# MainBoard_PERIPH.net
KiCad netlist of a schematic drawn in Altium Designer
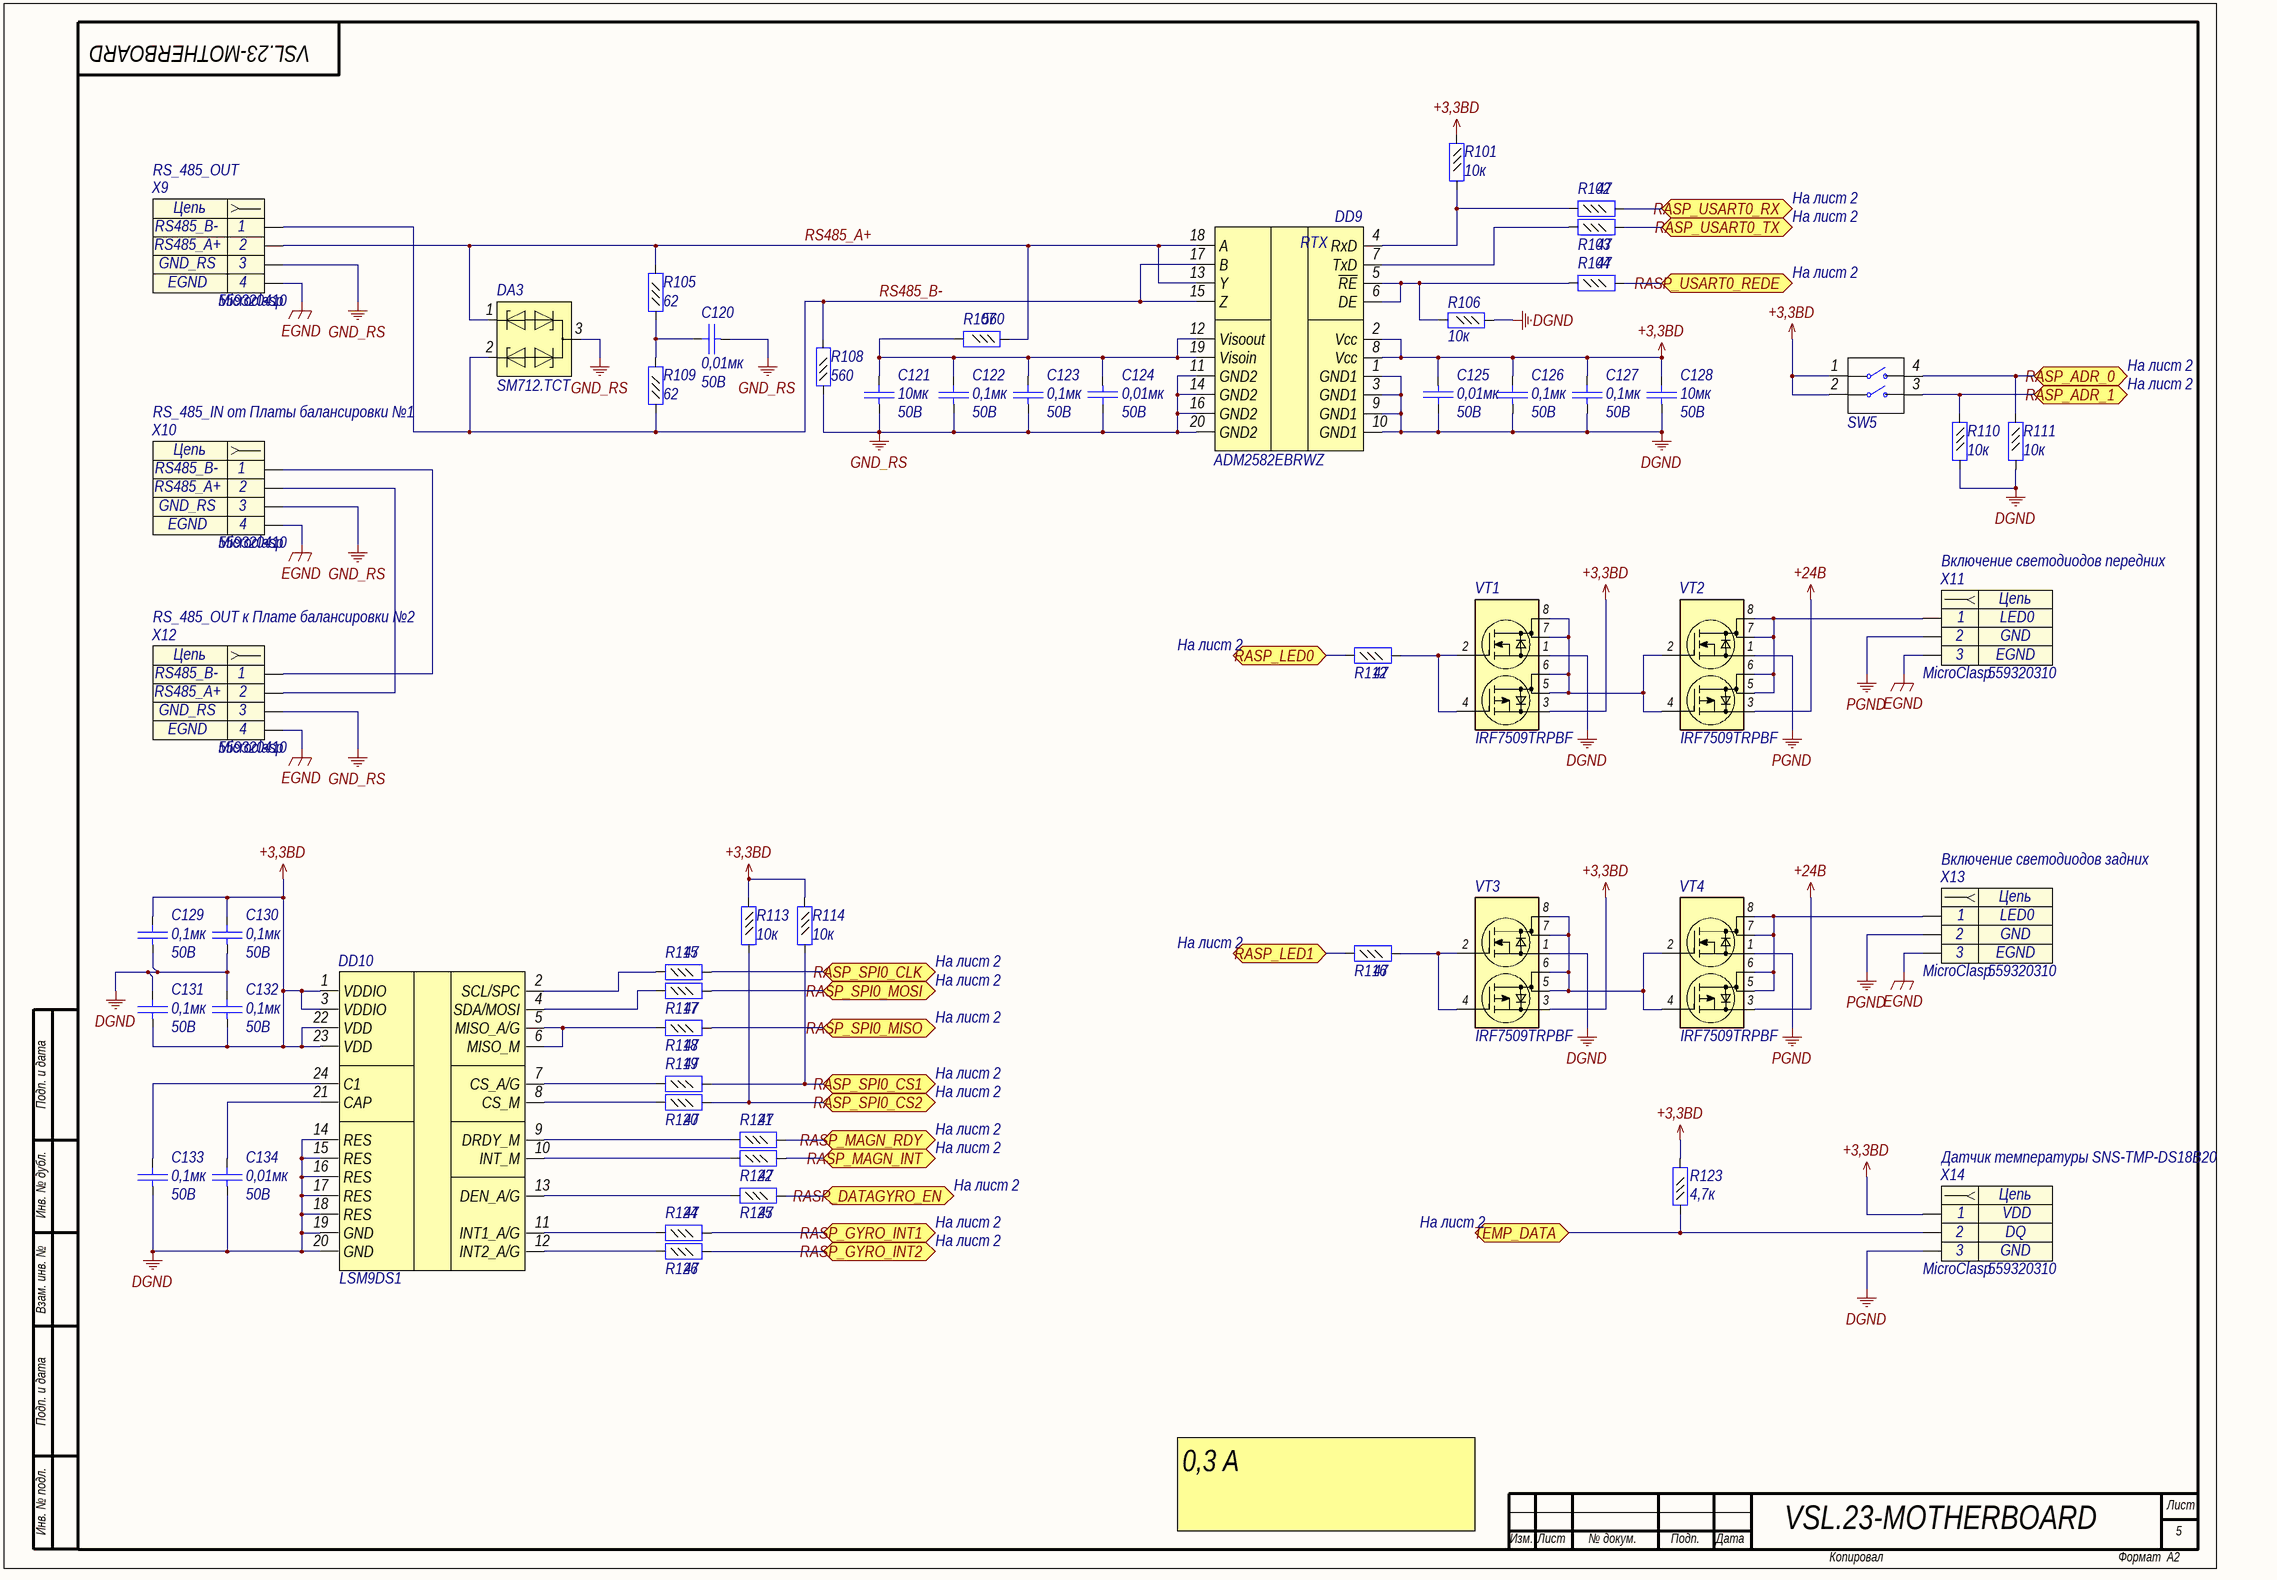
[diagram p0: MainBoard_PERIPH.SchDoc]

(export (version "E")
  (design (tool "Eeschema 10.0.6"))
  (components
    (comp (ref "C120")
      (value "0,01мк")
      (footprint "C0402")
      (description "Конденсатор")
      (fields
        (field (name "VOLTAGE") "50B")
        (field (name "PART NUMBER") "GRM155R71H103K")
        (field (name "Comment") "Capacitor")
      )
      (libsource (lib "MOP44") (part "Capacitor"))
    )
    (comp (ref "C121")
      (value "10мк")
      (footprint "C1210")
      (description "Конденсатор")
      (fields (field (name "VOLTAGE") "50В") (field (name "PART NUMBER") "C3225X7R1H106K250AC"))
      (libsource (lib "MOP44") (part "Capacitor"))
    )
    (comp (ref "C122")
      (value "0,1мк")
      (footprint "C0402")
      (description "Конденсатор")
      (fields
        (field (name "VOLTAGE") "50В")
        (field (name "PART NUMBER") "GRM155R71H104KE14D ")
        (field (name "Comment") "Capacitor")
      )
      (libsource (lib "MOP44") (part "Capacitor"))
    )
    (comp (ref "C123")
      (value "0,1мк")
      (footprint "C0402")
      (description "Конденсатор")
      (fields
        (field (name "VOLTAGE") "50В")
        (field (name "PART NUMBER") "GRM155R71H104KE14D ")
        (field (name "Comment") "Capacitor")
      )
      (libsource (lib "MOP44") (part "Capacitor"))
    )
    (comp (ref "C124")
      (value "0,01мк")
      (footprint "C0402")
      (description "Конденсатор")
      (fields (field (name "VOLTAGE") "50B") (field (name "PART NUMBER") "GRM155R71H103K"))
      (libsource (lib "MOP44") (part "Capacitor"))
    )
    (comp (ref "C125")
      (value "0,01мк")
      (footprint "C0402")
      (description "Конденсатор")
      (fields (field (name "VOLTAGE") "50B") (field (name "PART NUMBER") "GRM155R71H103K"))
      (libsource (lib "MOP44") (part "Capacitor"))
    )
    (comp (ref "C126")
      (value "0,1мк")
      (footprint "C0402")
      (description "Конденсатор")
      (fields
        (field (name "VOLTAGE") "50В")
        (field (name "PART NUMBER") "GRM155R71H104KE14D ")
        (field (name "Comment") "Capacitor")
      )
      (libsource (lib "MOP44") (part "Capacitor"))
    )
    (comp (ref "C127")
      (value "0,1мк")
      (footprint "C0402")
      (description "Конденсатор")
      (fields
        (field (name "VOLTAGE") "50В")
        (field (name "PART NUMBER") "GRM155R71H104KE14D ")
        (field (name "Comment") "Capacitor")
      )
      (libsource (lib "MOP44") (part "Capacitor"))
    )
    (comp (ref "C128")
      (value "10мк")
      (footprint "C1210")
      (description "Конденсатор")
      (fields (field (name "VOLTAGE") "50В") (field (name "PART NUMBER") "C3225X7R1H106K250AC"))
      (libsource (lib "MOP44") (part "Capacitor"))
    )
    (comp (ref "C129")
      (value "0,1мк")
      (footprint "C0402")
      (description "Конденсатор")
      (fields
        (field (name "VOLTAGE") "50В")
        (field (name "PART NUMBER") "GRM155R71H104KE14D ")
        (field (name "Comment") "Capacitor")
      )
      (libsource (lib "MOP44") (part "Capacitor"))
    )
    (comp (ref "C130")
      (value "0,1мк")
      (footprint "C0402")
      (description "Конденсатор")
      (fields
        (field (name "VOLTAGE") "50В")
        (field (name "PART NUMBER") "GRM155R71H104KE14D ")
        (field (name "Comment") "Capacitor")
      )
      (libsource (lib "MOP44") (part "Capacitor"))
    )
    (comp (ref "C131")
      (value "0,1мк")
      (footprint "C0402")
      (description "Конденсатор")
      (fields
        (field (name "VOLTAGE") "50В")
        (field (name "PART NUMBER") "GRM155R71H104KE14D ")
        (field (name "Comment") "Capacitor")
      )
      (libsource (lib "MOP44") (part "Capacitor"))
    )
    (comp (ref "C132")
      (value "0,1мк")
      (footprint "C0402")
      (description "Конденсатор")
      (fields
        (field (name "VOLTAGE") "50В")
        (field (name "PART NUMBER") "GRM155R71H104KE14D ")
        (field (name "Comment") "Capacitor")
      )
      (libsource (lib "MOP44") (part "Capacitor"))
    )
    (comp (ref "C133")
      (value "0,1мк")
      (footprint "C0402")
      (description "Конденсатор")
      (fields
        (field (name "VOLTAGE") "50В")
        (field (name "PART NUMBER") "GRM155R71H104KE14D ")
        (field (name "Comment") "Capacitor")
      )
      (libsource (lib "MOP44") (part "Capacitor"))
    )
    (comp (ref "C134")
      (value "0,01мк")
      (footprint "C0402")
      (description "Конденсатор")
      (fields (field (name "VOLTAGE") "50B") (field (name "PART NUMBER") "GRM155R71H103K"))
      (libsource (lib "MOP44") (part "Capacitor"))
    )
    (comp (ref "DA3")
      (value "SM712")
      (footprint "SOT23-3")
      (description "TVS")
      (fields (field (name "PART NUMBER") "SM712.TCT"))
      (libsource (lib "MOP44") (part "SM712"))
    )
    (comp (ref "DD9")
      (value "~")
      (footprint "SO20W")
      (description "Приемопередатчик RS485 изолированный")
      (fields (field (name "PART NUMBER") "ADM2582EBRWZ"))
      (libsource (lib "MOP44") (part "ADM2582E"))
    )
    (comp (ref "DD10")
      (value "LSM9DS1")
      (footprint "LGA24")
      (description "3D accelerometer, 3D gyroscope, 3D magnetometer")
      (libsource (lib "MOP44") (part "LSM9DS1"))
    )
    (comp (ref "R101")
      (value "10к")
      (footprint "R0402")
      (description "Резистор")
      (fields (field (name "PART NUMBER") "RC0402FR-0710KL") (field (name "POWER") "0,062Вт"))
      (libsource (lib "") (part "Resistor_0,062Вт_2"))
    )
    (comp (ref "R102")
      (value "47")
      (footprint "R0402")
      (description "Резистор")
      (fields (field (name "PART NUMBER") "RC0402FR-0747RL") (field (name "POWER") "0,062Вт"))
      (libsource (lib "MOP44") (part "Resistor_0,062Вт"))
    )
    (comp (ref "R103")
      (value "47")
      (footprint "R0402")
      (description "Резистор")
      (fields (field (name "PART NUMBER") "RC0402FR-0747RL") (field (name "POWER") "0,062Вт"))
      (libsource (lib "MOP44") (part "Resistor_0,062Вт"))
    )
    (comp (ref "R104")
      (value "47")
      (footprint "R0402")
      (description "Резистор")
      (fields (field (name "PART NUMBER") "RC0402FR-0747RL") (field (name "POWER") "0,062Вт"))
      (libsource (lib "MOP44") (part "Resistor_0,062Вт"))
    )
    (comp (ref "R105")
      (value "62")
      (footprint "R0402")
      (description "Резистор")
      (fields (field (name "PART NUMBER") "RC0402FR-0762RL") (field (name "POWER") "0,062Вт"))
      (libsource (lib "MOP44") (part "Resistor_0,062Вт"))
    )
    (comp (ref "R106")
      (value "10к")
      (footprint "R0402")
      (description "Резистор")
      (fields (field (name "PART NUMBER") "RC0402FR-0710KL") (field (name "POWER") "0,062Вт"))
      (libsource (lib "") (part "Resistor_0,062Вт_1"))
    )
    (comp (ref "R107")
      (value "560")
      (footprint "R0402")
      (description "Резистор")
      (fields (field (name "PART NUMBER") "RC0402FR-07560RL") (field (name "POWER") "0,062Вт"))
      (libsource (lib "") (part "Resistor_0,062Вт_1"))
    )
    (comp (ref "R108")
      (value "560")
      (footprint "R0402")
      (description "Резистор")
      (fields (field (name "PART NUMBER") "RC0402FR-07560RL") (field (name "POWER") "0,062Вт"))
      (libsource (lib "") (part "Resistor_0,062Вт_3"))
    )
    (comp (ref "R109")
      (value "62")
      (footprint "R0402")
      (description "Резистор")
      (fields (field (name "PART NUMBER") "RC0402FR-0762RL") (field (name "POWER") "0,062Вт"))
      (libsource (lib "MOP44") (part "Resistor_0,062Вт"))
    )
    (comp (ref "R110")
      (value "10к")
      (footprint "R0402")
      (description "Резистор")
      (fields (field (name "PART NUMBER") "RC0402FR-0710KL") (field (name "POWER") "0,062Вт"))
      (libsource (lib "") (part "Resistor_0,062Вт_2"))
    )
    (comp (ref "R111")
      (value "10к")
      (footprint "R0402")
      (description "Резистор")
      (fields (field (name "PART NUMBER") "RC0402FR-0710KL") (field (name "POWER") "0,062Вт"))
      (libsource (lib "") (part "Resistor_0,062Вт_2"))
    )
    (comp (ref "R112")
      (value "47")
      (footprint "R0402")
      (description "Резистор")
      (fields (field (name "PART NUMBER") "RC0402FR-0747RL") (field (name "POWER") "0,062Вт"))
      (libsource (lib "MOP44") (part "Resistor_0,062Вт"))
    )
    (comp (ref "R113")
      (value "10к")
      (footprint "R0402")
      (description "Резистор")
      (fields (field (name "PART NUMBER") "RC0402FR-0710KL") (field (name "POWER") "0,062Вт"))
      (libsource (lib "") (part "Resistor_0,062Вт_2"))
    )
    (comp (ref "R114")
      (value "10к")
      (footprint "R0402")
      (description "Резистор")
      (fields (field (name "PART NUMBER") "RC0402FR-0710KL") (field (name "POWER") "0,062Вт"))
      (libsource (lib "") (part "Resistor_0,062Вт_2"))
    )
    (comp (ref "R115")
      (value "47")
      (footprint "R0402")
      (description "Резистор")
      (fields (field (name "PART NUMBER") "RC0402FR-0747RL") (field (name "POWER") "0,062Вт"))
      (libsource (lib "MOP44") (part "Resistor_0,062Вт"))
    )
    (comp (ref "R116")
      (value "47")
      (footprint "R0402")
      (description "Резистор")
      (fields (field (name "PART NUMBER") "RC0402FR-0747RL") (field (name "POWER") "0,062Вт"))
      (libsource (lib "MOP44") (part "Resistor_0,062Вт"))
    )
    (comp (ref "R117")
      (value "47")
      (footprint "R0402")
      (description "Резистор")
      (fields (field (name "PART NUMBER") "RC0402FR-0747RL") (field (name "POWER") "0,062Вт"))
      (libsource (lib "MOP44") (part "Resistor_0,062Вт"))
    )
    (comp (ref "R118")
      (value "47")
      (footprint "R0402")
      (description "Резистор")
      (fields (field (name "PART NUMBER") "RC0402FR-0747RL") (field (name "POWER") "0,062Вт"))
      (libsource (lib "MOP44") (part "Resistor_0,062Вт"))
    )
    (comp (ref "R119")
      (value "47")
      (footprint "R0402")
      (description "Резистор")
      (fields (field (name "PART NUMBER") "RC0402FR-0747RL") (field (name "POWER") "0,062Вт"))
      (libsource (lib "MOP44") (part "Resistor_0,062Вт"))
    )
    (comp (ref "R120")
      (value "47")
      (footprint "R0402")
      (description "Резистор")
      (fields (field (name "PART NUMBER") "RC0402FR-0747RL") (field (name "POWER") "0,062Вт"))
      (libsource (lib "MOP44") (part "Resistor_0,062Вт"))
    )
    (comp (ref "R121")
      (value "47")
      (footprint "R0402")
      (description "Резистор")
      (fields (field (name "PART NUMBER") "RC0402FR-0747RL") (field (name "POWER") "0,062Вт"))
      (libsource (lib "MOP44") (part "Resistor_0,062Вт"))
    )
    (comp (ref "R122")
      (value "47")
      (footprint "R0402")
      (description "Резистор")
      (fields (field (name "PART NUMBER") "RC0402FR-0747RL") (field (name "POWER") "0,062Вт"))
      (libsource (lib "MOP44") (part "Resistor_0,062Вт"))
    )
    (comp (ref "R123")
      (value "4,7к")
      (footprint "R0402")
      (description "Резистор")
      (fields (field (name "PART NUMBER") "RC0402FR-074K7") (field (name "POWER") "0,062Вт"))
      (libsource (lib "") (part "Resistor_0,062Вт_3"))
    )
    (comp (ref "R124")
      (value "47")
      (footprint "R0402")
      (description "Резистор")
      (fields (field (name "PART NUMBER") "RC0402FR-0747RL") (field (name "POWER") "0,062Вт"))
      (libsource (lib "MOP44") (part "Resistor_0,062Вт"))
    )
    (comp (ref "R125")
      (value "47")
      (footprint "R0402")
      (description "Резистор")
      (fields (field (name "PART NUMBER") "RC0402FR-0747RL") (field (name "POWER") "0,062Вт"))
      (libsource (lib "MOP44") (part "Resistor_0,062Вт"))
    )
    (comp (ref "R126")
      (value "47")
      (footprint "R0402")
      (description "Резистор")
      (fields (field (name "PART NUMBER") "RC0402FR-0747RL") (field (name "POWER") "0,062Вт"))
      (libsource (lib "MOP44") (part "Resistor_0,062Вт"))
    )
    (comp (ref "SW5")
      (value "DS1040-02")
      (footprint "2PAD_ADR")
      (description "DIP переключатель")
      (libsource (lib "MOP44") (part "DS1040-02"))
    )
    (comp (ref "VT1")
      (value "IRF7509TRPBF")
      (footprint "Micro8")
      (description "Комплементарная сборка МОП")
      (fields
        (field (name "PART NUMBER") "IRF7509TRPBF")
        (field (name "MANUFACTURER") "International Rectifier")
      )
      (libsource (lib "MOP44") (part "IRF7509TRPBF"))
    )
    (comp (ref "VT2")
      (value "IRF7509TRPBF")
      (footprint "Micro8")
      (description "Комплементарная сборка МОП")
      (fields
        (field (name "PART NUMBER") "IRF7509TRPBF")
        (field (name "MANUFACTURER") "International Rectifier")
      )
      (libsource (lib "MOP44") (part "IRF7509TRPBF"))
    )
    (comp (ref "VT3")
      (value "IRF7509TRPBF")
      (footprint "Micro8")
      (description "Комплементарная сборка МОП")
      (fields
        (field (name "PART NUMBER") "IRF7509TRPBF")
        (field (name "MANUFACTURER") "International Rectifier")
      )
      (libsource (lib "MOP44") (part "IRF7509TRPBF"))
    )
    (comp (ref "VT4")
      (value "IRF7509TRPBF")
      (footprint "Micro8")
      (description "Комплементарная сборка МОП")
      (fields
        (field (name "PART NUMBER") "IRF7509TRPBF")
        (field (name "MANUFACTURER") "International Rectifier")
      )
      (libsource (lib "MOP44") (part "IRF7509TRPBF"))
    )
    (comp (ref "X9")
      (value "RS_485_OUT")
      (footprint "MOLEX_559320410")
      (description "Разъем - 4 конт. розетка")
      (fields (field (name "PART NUMBER") "559320410"))
      (libsource (lib "MOP44") (part "Header_4_sct"))
    )
    (comp (ref "X10")
      (value "RS_485_IN от Платы балансировки №1")
      (footprint "MOLEX_559320410")
      (description "Разъем - 4 конт. розетка")
      (fields (field (name "PART NUMBER") "559320410"))
      (libsource (lib "MOP44") (part "Header_4_sct"))
    )
    (comp (ref "X11")
      (value "Включение светодиодов передних")
      (footprint "MOLEX_559320310")
      (description "Разъем - 3 конт. розетка")
      (fields (field (name "PART NAME") "MicroClasp") (field (name "PART NUMBER") "559320310"))
      (libsource (lib "MOP44") (part "Header_3_sct"))
    )
    (comp (ref "X12")
      (value "RS_485_OUT к Плате балансировки №2")
      (footprint "MOLEX_559320410")
      (description "Разъем - 4 конт. розетка")
      (fields (field (name "PART NUMBER") "559320410"))
      (libsource (lib "MOP44") (part "Header_4_sct"))
    )
    (comp (ref "X13")
      (value "Включение светодиодов задних")
      (footprint "MOLEX_559320310")
      (description "Разъем - 3 конт. розетка")
      (fields (field (name "PART NAME") "MicroClasp") (field (name "PART NUMBER") "559320310"))
      (libsource (lib "MOP44") (part "Header_3_sct"))
    )
    (comp (ref "X14")
      (value "Датчик температуры SNS-TMP-DS18B20")
      (footprint "MOLEX_559320310")
      (description "Разъем - 3 конт. розетка")
      (fields (field (name "PART NAME") "MicroClasp") (field (name "PART NUMBER") "559320310"))
      (libsource (lib "MOP44") (part "Header_3_sct"))
    )
  )
  (nets
    (net (code "1") (name "+3,3BD") (class "Default")
      (node (ref "C125") (pin "1") (pinfunction "1_1") (pintype "passive"))
      (node (ref "C126") (pin "2") (pinfunction "2_2") (pintype "passive"))
      (node (ref "C127") (pin "2") (pinfunction "2_2") (pintype "passive"))
      (node (ref "C128") (pin "2") (pinfunction "2_2") (pintype "passive"))
      (node (ref "C129") (pin "2") (pinfunction "2_2") (pintype "passive"))
      (node (ref "C130") (pin "2") (pinfunction "2_2") (pintype "passive"))
      (node (ref "C131") (pin "1") (pinfunction "1_1") (pintype "passive"))
      (node (ref "C132") (pin "1") (pinfunction "1_1") (pintype "passive"))
      (node (ref "DD10") (pin "1") (pinfunction "VDDIO_1") (pintype "passive"))
      (node (ref "DD10") (pin "22") (pinfunction "VDD_22") (pintype "passive"))
      (node (ref "DD10") (pin "23") (pinfunction "VDD_23") (pintype "passive"))
      (node (ref "DD10") (pin "3") (pinfunction "VDDIO_3") (pintype "passive"))
      (node (ref "DD9") (pin "2") (pinfunction "Vcc_2") (pintype "passive"))
      (node (ref "DD9") (pin "8") (pinfunction "Vcc_8") (pintype "passive"))
      (node (ref "R101") (pin "1") (pinfunction "1_1") (pintype "passive"))
      (node (ref "R113") (pin "1") (pinfunction "1_1") (pintype "passive"))
      (node (ref "R114") (pin "1") (pinfunction "1_1") (pintype "passive"))
      (node (ref "R123") (pin "2") (pinfunction "2_2") (pintype "passive"))
      (node (ref "SW5") (pin "1") (pintype "passive"))
      (node (ref "SW5") (pin "2") (pintype "passive"))
      (node (ref "VT1") (pin "3") (pinfunction "S2_3") (pintype "passive"))
      (node (ref "VT3") (pin "3") (pinfunction "S2_3") (pintype "passive"))
      (node (ref "X14") (pin "1") (pinfunction "1_1") (pintype "passive"))
    )
    (net (code "2") (name "+24B") (class "Default")
      (node (ref "VT2") (pin "3") (pinfunction "S2_3") (pintype "passive"))
      (node (ref "VT4") (pin "3") (pinfunction "S2_3") (pintype "passive"))
    )
    (net (code "3") (name "/RASP_ADR_0") (class "Default")
      (node (ref "R111") (pin "1") (pinfunction "1_1") (pintype "passive"))
      (node (ref "SW5") (pin "4") (pintype "passive"))
    )
    (net (code "4") (name "/RASP_ADR_1") (class "Default")
      (node (ref "R110") (pin "1") (pinfunction "1_1") (pintype "passive"))
      (node (ref "SW5") (pin "3") (pintype "passive"))
    )
    (net (code "5") (name "/RASP_DATAGYRO_EN") (class "Default")
      (node (ref "R125") (pin "2") (pinfunction "2_2") (pintype "passive"))
    )
    (net (code "6") (name "/RASP_GYRO_INT1") (class "Default")
      (node (ref "R124") (pin "2") (pinfunction "2_2") (pintype "passive"))
    )
    (net (code "7") (name "/RASP_GYRO_INT2") (class "Default")
      (node (ref "R126") (pin "2") (pinfunction "2_2") (pintype "passive"))
    )
    (net (code "8") (name "/RASP_LED0") (class "Default")
      (node (ref "R112") (pin "1") (pinfunction "1_1") (pintype "passive"))
    )
    (net (code "9") (name "/RASP_LED1") (class "Default")
      (node (ref "R116") (pin "1") (pinfunction "1_1") (pintype "passive"))
    )
    (net (code "10") (name "/RASP_MAGN_INT") (class "Default")
      (node (ref "R122") (pin "2") (pinfunction "2_2") (pintype "passive"))
    )
    (net (code "11") (name "/RASP_MAGN_RDY") (class "Default")
      (node (ref "R121") (pin "2") (pinfunction "2_2") (pintype "passive"))
    )
    (net (code "12") (name "/RASP_SPI0_CLK") (class "Default")
      (node (ref "R115") (pin "2") (pinfunction "2_2") (pintype "passive"))
    )
    (net (code "13") (name "/RASP_SPI0_CS1") (class "Default")
      (node (ref "R114") (pin "2") (pinfunction "2_2") (pintype "passive"))
      (node (ref "R119") (pin "2") (pinfunction "2_2") (pintype "passive"))
    )
    (net (code "14") (name "/RASP_SPI0_CS2") (class "Default")
      (node (ref "R113") (pin "2") (pinfunction "2_2") (pintype "passive"))
      (node (ref "R120") (pin "2") (pinfunction "2_2") (pintype "passive"))
    )
    (net (code "15") (name "/RASP_SPI0_MISO") (class "Default")
      (node (ref "R118") (pin "2") (pinfunction "2_2") (pintype "passive"))
    )
    (net (code "16") (name "/RASP_SPI0_MOSI") (class "Default")
      (node (ref "R117") (pin "2") (pinfunction "2_2") (pintype "passive"))
    )
    (net (code "17") (name "/RASP_USART0_REDE") (class "Default")
      (node (ref "R104") (pin "2") (pinfunction "2_2") (pintype "passive"))
    )
    (net (code "18") (name "/RASP_USART0_RX") (class "Default")
      (node (ref "R102") (pin "2") (pinfunction "2_2") (pintype "passive"))
    )
    (net (code "19") (name "/RASP_USART0_TX") (class "Default")
      (node (ref "R103") (pin "2") (pinfunction "2_2") (pintype "passive"))
    )
    (net (code "20") (name "/RS485_A+") (class "Default")
      (node (ref "DA3") (pin "1") (pintype "passive"))
      (node (ref "DD9") (pin "13") (pinfunction "Y_13") (pintype "passive"))
      (node (ref "DD9") (pin "18") (pinfunction "A_18") (pintype "passive"))
      (node (ref "R105") (pin "2") (pinfunction "2_2") (pintype "passive"))
      (node (ref "R107") (pin "1") (pinfunction "1_1") (pintype "passive"))
      (node (ref "X9") (pin "2") (pinfunction "2_2") (pintype "passive"))
    )
    (net (code "21") (name "/RS485_B-") (class "Default")
      (node (ref "DA3") (pin "2") (pinfunction "1_2") (pintype "passive"))
      (node (ref "DD9") (pin "15") (pinfunction "Z_15") (pintype "passive"))
      (node (ref "DD9") (pin "17") (pinfunction "B_17") (pintype "passive"))
      (node (ref "R108") (pin "2") (pinfunction "2_2") (pintype "passive"))
      (node (ref "R109") (pin "1") (pinfunction "1_1") (pintype "passive"))
      (node (ref "X9") (pin "1") (pinfunction "1_1") (pintype "passive"))
    )
    (net (code "22") (name "/TEMP_DATA") (class "Default")
      (node (ref "R123") (pin "1") (pinfunction "1_1") (pintype "passive"))
      (node (ref "X14") (pin "2") (pinfunction "2_2") (pintype "passive"))
    )
    (net (code "23") (name "DGND") (class "Default")
      (node (ref "C125") (pin "2") (pinfunction "2_2") (pintype "passive"))
      (node (ref "C126") (pin "1") (pinfunction "1_1") (pintype "passive"))
      (node (ref "C127") (pin "1") (pinfunction "1_1") (pintype "passive"))
      (node (ref "C128") (pin "1") (pinfunction "1_1") (pintype "passive"))
      (node (ref "C129") (pin "1") (pinfunction "1_1") (pintype "passive"))
      (node (ref "C130") (pin "1") (pinfunction "1_1") (pintype "passive"))
      (node (ref "C131") (pin "2") (pinfunction "2_2") (pintype "passive"))
      (node (ref "C132") (pin "2") (pinfunction "2_2") (pintype "passive"))
      (node (ref "C133") (pin "1") (pinfunction "1_1") (pintype "passive"))
      (node (ref "C134") (pin "1") (pinfunction "1_1") (pintype "passive"))
      (node (ref "DD10") (pin "14") (pinfunction "RES_14") (pintype "passive"))
      (node (ref "DD10") (pin "15") (pinfunction "RES_15") (pintype "passive"))
      (node (ref "DD10") (pin "16") (pinfunction "RES_16") (pintype "passive"))
      (node (ref "DD10") (pin "17") (pinfunction "RES_17") (pintype "passive"))
      (node (ref "DD10") (pin "18") (pinfunction "RES_18") (pintype "passive"))
      (node (ref "DD10") (pin "19") (pinfunction "GND_19") (pintype "passive"))
      (node (ref "DD10") (pin "20") (pinfunction "GND_20") (pintype "passive"))
      (node (ref "DD9") (pin "1") (pinfunction "GND1_1") (pintype "passive"))
      (node (ref "DD9") (pin "10") (pinfunction "GND1_10") (pintype "passive"))
      (node (ref "DD9") (pin "3") (pinfunction "GND1_3") (pintype "passive"))
      (node (ref "DD9") (pin "9") (pinfunction "GND1_9") (pintype "passive"))
      (node (ref "R106") (pin "1") (pinfunction "1_1") (pintype "passive"))
      (node (ref "R110") (pin "2") (pinfunction "2_2") (pintype "passive"))
      (node (ref "R111") (pin "2") (pinfunction "2_2") (pintype "passive"))
      (node (ref "VT1") (pin "1") (pinfunction "S1_1") (pintype "passive"))
      (node (ref "VT3") (pin "1") (pinfunction "S1_1") (pintype "passive"))
      (node (ref "X14") (pin "3") (pinfunction "3_3") (pintype "passive"))
    )
    (net (code "24") (name "EGND") (class "Default")
      (node (ref "X10") (pin "4") (pinfunction "4_4") (pintype "passive"))
      (node (ref "X11") (pin "3") (pinfunction "3_3") (pintype "passive"))
      (node (ref "X12") (pin "4") (pinfunction "4_4") (pintype "passive"))
      (node (ref "X13") (pin "3") (pinfunction "3_3") (pintype "passive"))
      (node (ref "X9") (pin "4") (pinfunction "4_4") (pintype "passive"))
    )
    (net (code "25") (name "GND_RS") (class "Default")
      (node (ref "C120") (pin "1") (pinfunction "1_1") (pintype "passive"))
      (node (ref "C121") (pin "1") (pinfunction "1_1") (pintype "passive"))
      (node (ref "C122") (pin "1") (pinfunction "1_1") (pintype "passive"))
      (node (ref "C123") (pin "1") (pinfunction "1_1") (pintype "passive"))
      (node (ref "C124") (pin "2") (pinfunction "2_2") (pintype "passive"))
      (node (ref "DA3") (pin "3") (pintype "passive"))
      (node (ref "DD9") (pin "11") (pinfunction "GND2_11") (pintype "passive"))
      (node (ref "DD9") (pin "14") (pinfunction "GND2_14") (pintype "passive"))
      (node (ref "DD9") (pin "16") (pinfunction "GND2_16") (pintype "passive"))
      (node (ref "DD9") (pin "20") (pinfunction "GND2_20") (pintype "passive"))
      (node (ref "R108") (pin "1") (pinfunction "1_1") (pintype "passive"))
      (node (ref "X10") (pin "3") (pinfunction "3_3") (pintype "passive"))
      (node (ref "X12") (pin "3") (pinfunction "3_3") (pintype "passive"))
      (node (ref "X9") (pin "3") (pinfunction "3_3") (pintype "passive"))
    )
    (net (code "26") (name "Net-(C120-Pad2)") (class "Default")
      (node (ref "C120") (pin "2") (pinfunction "2_2") (pintype "passive"))
      (node (ref "R105") (pin "1") (pinfunction "1_1") (pintype "passive"))
      (node (ref "R109") (pin "2") (pinfunction "2_2") (pintype "passive"))
    )
    (net (code "27") (name "Net-(DD9-DE)") (class "Default")
      (node (ref "DD9") (pin "5") (pinfunction "~{RE}_5") (pintype "passive"))
      (node (ref "DD9") (pin "6") (pinfunction "DE_6") (pintype "passive"))
      (node (ref "R104") (pin "1") (pinfunction "1_1") (pintype "passive"))
      (node (ref "R106") (pin "2") (pinfunction "2_2") (pintype "passive"))
    )
    (net (code "28") (name "Net-(DD9-RxD)") (class "Default")
      (node (ref "DD9") (pin "4") (pinfunction "RxD_4") (pintype "passive"))
      (node (ref "R101") (pin "2") (pinfunction "2_2") (pintype "passive"))
      (node (ref "R102") (pin "1") (pinfunction "1_1") (pintype "passive"))
    )
    (net (code "29") (name "Net-(DD9-TxD)") (class "Default")
      (node (ref "DD9") (pin "7") (pinfunction "TxD_7") (pintype "passive"))
      (node (ref "R103") (pin "1") (pinfunction "1_1") (pintype "passive"))
    )
    (net (code "30") (name "Net-(DD9-Visoin)") (class "Default")
      (node (ref "C121") (pin "2") (pinfunction "2_2") (pintype "passive"))
      (node (ref "C122") (pin "2") (pinfunction "2_2") (pintype "passive"))
      (node (ref "C123") (pin "2") (pinfunction "2_2") (pintype "passive"))
      (node (ref "C124") (pin "1") (pinfunction "1_1") (pintype "passive"))
      (node (ref "DD9") (pin "12") (pinfunction "Visoout_12") (pintype "passive"))
      (node (ref "DD9") (pin "19") (pinfunction "Visoin_19") (pintype "passive"))
      (node (ref "R107") (pin "2") (pinfunction "2_2") (pintype "passive"))
    )
    (net (code "31") (name "Net-(DD10-C1)") (class "Default")
      (node (ref "C133") (pin "2") (pinfunction "2_2") (pintype "passive"))
      (node (ref "DD10") (pin "24") (pinfunction "C1_24") (pintype "passive"))
    )
    (net (code "32") (name "Net-(DD10-CAP)") (class "Default")
      (node (ref "C134") (pin "2") (pinfunction "2_2") (pintype "passive"))
      (node (ref "DD10") (pin "21") (pinfunction "CAP_21") (pintype "passive"))
    )
    (net (code "33") (name "Net-(DD10-CS_A{slash}G)") (class "Default")
      (node (ref "DD10") (pin "7") (pinfunction "CS_A/G_7") (pintype "passive"))
      (node (ref "R119") (pin "1") (pinfunction "1_1") (pintype "passive"))
    )
    (net (code "34") (name "Net-(DD10-CS_M)") (class "Default")
      (node (ref "DD10") (pin "8") (pinfunction "CS_M_8") (pintype "passive"))
      (node (ref "R120") (pin "1") (pinfunction "1_1") (pintype "passive"))
    )
    (net (code "35") (name "Net-(DD10-DEN_A{slash}G)") (class "Default")
      (node (ref "DD10") (pin "13") (pinfunction "DEN_A/G_13") (pintype "passive"))
      (node (ref "R125") (pin "1") (pinfunction "1_1") (pintype "passive"))
    )
    (net (code "36") (name "Net-(DD10-DRDY_M)") (class "Default")
      (node (ref "DD10") (pin "9") (pinfunction "DRDY_M_9") (pintype "passive"))
      (node (ref "R121") (pin "1") (pinfunction "1_1") (pintype "passive"))
    )
    (net (code "37") (name "Net-(DD10-INT1_A{slash}G)") (class "Default")
      (node (ref "DD10") (pin "11") (pinfunction "INT1_A/G_11") (pintype "passive"))
      (node (ref "R124") (pin "1") (pinfunction "1_1") (pintype "passive"))
    )
    (net (code "38") (name "Net-(DD10-INT2_A{slash}G)") (class "Default")
      (node (ref "DD10") (pin "12") (pinfunction "INT2_A/G_12") (pintype "passive"))
      (node (ref "R126") (pin "1") (pinfunction "1_1") (pintype "passive"))
    )
    (net (code "39") (name "Net-(DD10-INT_M)") (class "Default")
      (node (ref "DD10") (pin "10") (pinfunction "INT_M_10") (pintype "passive"))
      (node (ref "R122") (pin "1") (pinfunction "1_1") (pintype "passive"))
    )
    (net (code "40") (name "Net-(DD10-MISO_A{slash}G)") (class "Default")
      (node (ref "DD10") (pin "5") (pinfunction "MISO_A/G_5") (pintype "passive"))
      (node (ref "DD10") (pin "6") (pinfunction "MISO_M_6") (pintype "passive"))
      (node (ref "R118") (pin "1") (pinfunction "1_1") (pintype "passive"))
    )
    (net (code "41") (name "Net-(DD10-SCL{slash}SPC)") (class "Default")
      (node (ref "DD10") (pin "2") (pinfunction "SCL/SPC_2") (pintype "passive"))
      (node (ref "R115") (pin "1") (pinfunction "1_1") (pintype "passive"))
    )
    (net (code "42") (name "Net-(DD10-SDA{slash}MOSI)") (class "Default")
      (node (ref "DD10") (pin "4") (pinfunction "SDA/MOSI_4") (pintype "passive"))
      (node (ref "R117") (pin "1") (pinfunction "1_1") (pintype "passive"))
    )
    (net (code "43") (name "Net-(VT1-G1)") (class "Default")
      (node (ref "R112") (pin "2") (pinfunction "2_2") (pintype "passive"))
      (node (ref "VT1") (pin "2") (pinfunction "G1_2") (pintype "passive"))
      (node (ref "VT1") (pin "4") (pinfunction "G2_4") (pintype "passive"))
    )
    (net (code "44") (name "Net-(VT2-D1-Pad7)") (class "Default")
      (node (ref "VT2") (pin "5") (pinfunction "D2_5") (pintype "passive"))
      (node (ref "VT2") (pin "6") (pinfunction "D2_6") (pintype "passive"))
      (node (ref "VT2") (pin "7") (pinfunction "D1_7") (pintype "passive"))
      (node (ref "VT2") (pin "8") (pinfunction "D1_8") (pintype "passive"))
      (node (ref "X11") (pin "1") (pinfunction "1_1") (pintype "passive"))
    )
    (net (code "45") (name "Net-(VT2-G1)") (class "Default")
      (node (ref "VT1") (pin "5") (pinfunction "D2_5") (pintype "passive"))
      (node (ref "VT1") (pin "6") (pinfunction "D2_6") (pintype "passive"))
      (node (ref "VT1") (pin "7") (pinfunction "D1_7") (pintype "passive"))
      (node (ref "VT1") (pin "8") (pinfunction "D1_8") (pintype "passive"))
      (node (ref "VT2") (pin "2") (pinfunction "G1_2") (pintype "passive"))
      (node (ref "VT2") (pin "4") (pinfunction "G2_4") (pintype "passive"))
    )
    (net (code "46") (name "Net-(VT3-G1)") (class "Default")
      (node (ref "R116") (pin "2") (pinfunction "2_2") (pintype "passive"))
      (node (ref "VT3") (pin "2") (pinfunction "G1_2") (pintype "passive"))
      (node (ref "VT3") (pin "4") (pinfunction "G2_4") (pintype "passive"))
    )
    (net (code "47") (name "Net-(VT4-D1-Pad7)") (class "Default")
      (node (ref "VT4") (pin "5") (pinfunction "D2_5") (pintype "passive"))
      (node (ref "VT4") (pin "6") (pinfunction "D2_6") (pintype "passive"))
      (node (ref "VT4") (pin "7") (pinfunction "D1_7") (pintype "passive"))
      (node (ref "VT4") (pin "8") (pinfunction "D1_8") (pintype "passive"))
      (node (ref "X13") (pin "1") (pinfunction "1_1") (pintype "passive"))
    )
    (net (code "48") (name "Net-(VT4-G1)") (class "Default")
      (node (ref "VT3") (pin "5") (pinfunction "D2_5") (pintype "passive"))
      (node (ref "VT3") (pin "6") (pinfunction "D2_6") (pintype "passive"))
      (node (ref "VT3") (pin "7") (pinfunction "D1_7") (pintype "passive"))
      (node (ref "VT3") (pin "8") (pinfunction "D1_8") (pintype "passive"))
      (node (ref "VT4") (pin "2") (pinfunction "G1_2") (pintype "passive"))
      (node (ref "VT4") (pin "4") (pinfunction "G2_4") (pintype "passive"))
    )
    (net (code "49") (name "Net-(X10-Pad1)") (class "Default")
      (node (ref "X10") (pin "1") (pinfunction "1_1") (pintype "passive"))
      (node (ref "X12") (pin "1") (pinfunction "1_1") (pintype "passive"))
    )
    (net (code "50") (name "Net-(X10-Pad2)") (class "Default")
      (node (ref "X10") (pin "2") (pinfunction "2_2") (pintype "passive"))
      (node (ref "X12") (pin "2") (pinfunction "2_2") (pintype "passive"))
    )
    (net (code "51") (name "PGND") (class "Default")
      (node (ref "VT2") (pin "1") (pinfunction "S1_1") (pintype "passive"))
      (node (ref "VT4") (pin "1") (pinfunction "S1_1") (pintype "passive"))
      (node (ref "X11") (pin "2") (pinfunction "2_2") (pintype "passive"))
      (node (ref "X13") (pin "2") (pinfunction "2_2") (pintype "passive"))
    )
  )
)
